# APRS-ESP32_SA8x8_Rev_C.net
KiCad netlist of a schematic drawn in EAGLE
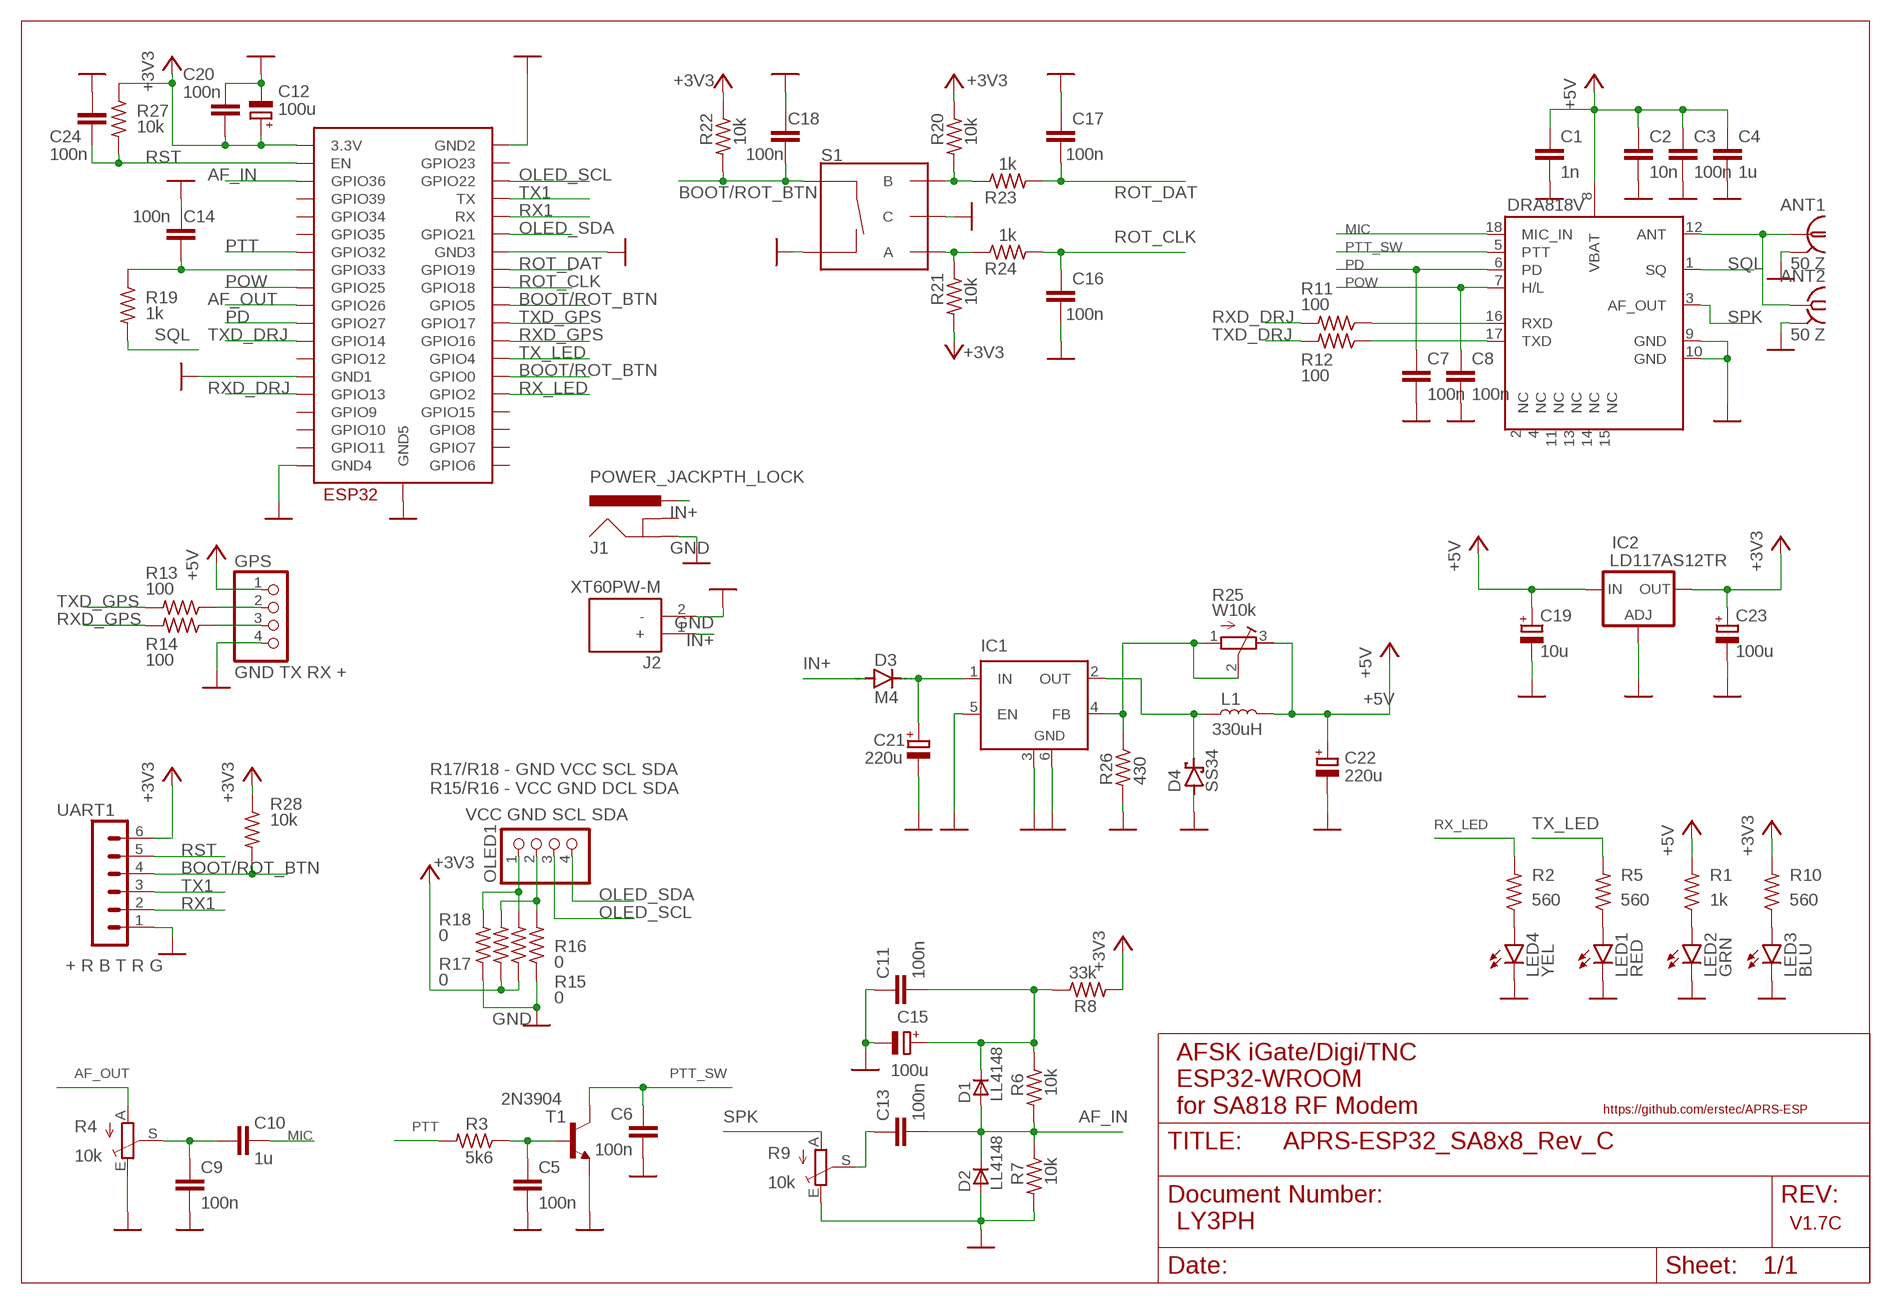
[diagram p0: schematic, sheet 1]

(export (version "E")
  (design (tool "Eeschema 10.0.6"))
  (components
    (comp (ref "ANT1")
      (value "50 Z")
      (footprint "eagle-import:LTI-SASF54GT")
      (libsource (lib "eagle-import") (part "LTI-SASF54GT"))
    )
    (comp (ref "ANT2")
      (value "50 Z")
      (footprint "eagle-import:J502-ND-142-0701-801_806")
      (fields (field (name "MF") "JOHNSON COMPONENTS") (field (name "MPN") "142-0701-801"))
      (libsource (lib "eagle-import") (part "SMA-142-0701-801/806"))
    )
    (comp (ref "C1")
      (value "1n")
      (footprint "eagle-import:C0805")
      (libsource (lib "eagle-import") (part "C-EUC0805"))
    )
    (comp (ref "C2")
      (value "10n")
      (footprint "eagle-import:C0805")
      (libsource (lib "eagle-import") (part "C-EUC0805"))
    )
    (comp (ref "C3")
      (value "100n")
      (footprint "eagle-import:C0805")
      (libsource (lib "eagle-import") (part "C-EUC0805"))
    )
    (comp (ref "C4")
      (value "1u")
      (footprint "eagle-import:C0805")
      (libsource (lib "eagle-import") (part "C-EUC0805"))
    )
    (comp (ref "C5")
      (value "100n")
      (footprint "eagle-import:C0805")
      (libsource (lib "eagle-import") (part "C-EUC0805"))
    )
    (comp (ref "C6")
      (value "100n")
      (footprint "eagle-import:C0805")
      (libsource (lib "eagle-import") (part "C-EUC0805"))
    )
    (comp (ref "C7")
      (value "100n")
      (footprint "eagle-import:C0805")
      (libsource (lib "eagle-import") (part "C-EUC0805"))
    )
    (comp (ref "C8")
      (value "100n")
      (footprint "eagle-import:C0805")
      (libsource (lib "eagle-import") (part "C-EUC0805"))
    )
    (comp (ref "C9")
      (value "100n")
      (footprint "eagle-import:C0805")
      (libsource (lib "eagle-import") (part "C-EUC0805"))
    )
    (comp (ref "C10")
      (value "1u")
      (footprint "eagle-import:C0805")
      (libsource (lib "eagle-import") (part "C-EUC0805"))
    )
    (comp (ref "C11")
      (value "100n")
      (footprint "eagle-import:C0805")
      (libsource (lib "eagle-import") (part "C-EUC0805"))
    )
    (comp (ref "C12")
      (value "100u")
      (footprint "eagle-import:SMC_D")
      (libsource (lib "eagle-import") (part "CPOL-EUSMCD"))
    )
    (comp (ref "C13")
      (value "100n")
      (footprint "eagle-import:C0805")
      (libsource (lib "eagle-import") (part "C-EUC0805"))
    )
    (comp (ref "C14")
      (value "100n")
      (footprint "eagle-import:C0805")
      (libsource (lib "eagle-import") (part "C-EUC0805"))
    )
    (comp (ref "C15")
      (value "100u")
      (footprint "eagle-import:SMC_D")
      (libsource (lib "eagle-import") (part "CPOL-EUSMCD"))
    )
    (comp (ref "C16")
      (value "100n")
      (footprint "eagle-import:C0805")
      (libsource (lib "eagle-import") (part "C-EUC0805"))
    )
    (comp (ref "C17")
      (value "100n")
      (footprint "eagle-import:C0805")
      (libsource (lib "eagle-import") (part "C-EUC0805"))
    )
    (comp (ref "C18")
      (value "100n")
      (footprint "eagle-import:C0805")
      (libsource (lib "eagle-import") (part "C-EUC0805"))
    )
    (comp (ref "C19")
      (value "10u")
      (footprint "eagle-import:PANASONIC_B")
      (libsource (lib "eagle-import") (part "CPOL-EUB"))
    )
    (comp (ref "C20")
      (value "100n")
      (footprint "eagle-import:C0805")
      (libsource (lib "eagle-import") (part "C-EUC0805"))
    )
    (comp (ref "C21")
      (value "220u")
      (footprint "eagle-import:175TMP-0808")
      (libsource (lib "eagle-import") (part "CPOL-EU175TMP-0808"))
    )
    (comp (ref "C22")
      (value "220u")
      (footprint "eagle-import:175TMP-0808")
      (libsource (lib "eagle-import") (part "CPOL-EU175TMP-0808"))
    )
    (comp (ref "C23")
      (value "100u")
      (footprint "eagle-import:PANASONIC_B")
      (libsource (lib "eagle-import") (part "CPOL-EUB"))
    )
    (comp (ref "C24")
      (value "100n")
      (footprint "eagle-import:C0805")
      (libsource (lib "eagle-import") (part "C-EUC0805"))
    )
    (comp (ref "D1")
      (value "LL4148")
      (footprint "eagle-import:SOD80_DO213AA_MINIMELF")
      (libsource (lib "eagle-import") (part "LL4148"))
    )
    (comp (ref "D2")
      (value "LL4148")
      (footprint "eagle-import:SOD80_DO213AA_MINIMELF")
      (libsource (lib "eagle-import") (part "LL4148"))
    )
    (comp (ref "D3")
      (value "M4")
      (footprint "eagle-import:SMB")
      (libsource (lib "eagle-import") (part "DIODE-SMB"))
    )
    (comp (ref "D4")
      (value "SS34")
      (footprint "eagle-import:SMB")
      (libsource (lib "eagle-import") (part "SCHOTTKY-DIODESMD"))
    )
    (comp (ref "DRA818V")
      (value "DRA818A")
      (footprint "eagle-import:DRA818A")
      (libsource (lib "eagle-import") (part "DRA818A"))
    )
    (comp (ref "GPS")
      (value "GND TX RX +")
      (footprint "eagle-import:1X04")
      (libsource (lib "eagle-import") (part "PINHD-1X4"))
    )
    (comp (ref "IC1")
      (value "LM2596S")
      (footprint "eagle-import:TO263-5")
      (libsource (lib "eagle-import") (part "LM2596S"))
    )
    (comp (ref "IC2")
      (value "LD117AS12TR")
      (footprint "eagle-import:SOT223")
      (libsource (lib "eagle-import") (part "LD117A?S12TR"))
    )
    (comp (ref "J1")
      (value "POWER_JACKPTH_LOCK")
      (footprint "eagle-import:POWER_JACK_PTH_LOCK")
      (libsource (lib "eagle-import") (part "POWER_JACKPTH_LOCK"))
    )
    (comp (ref "J2")
      (value "XT60PW-M")
      (footprint "eagle-import:AMASS_XT60PW-M")
      (fields (field (name "MF") "AMASS"))
      (libsource (lib "eagle-import") (part "XT60PW-M"))
    )
    (comp (ref "L1")
      (value "330uH")
      (footprint "eagle-import:INDUCTOR_SDR1307")
      (libsource (lib "eagle-import") (part "INDUCTOR-SDR13-27UH"))
    )
    (comp (ref "LED1")
      (value "RED")
      (footprint "eagle-import:CHIP-LED0805")
      (libsource (lib "eagle-import") (part "LEDCHIP-LED0805"))
    )
    (comp (ref "LED2")
      (value "GRN")
      (footprint "eagle-import:CHIP-LED0805")
      (libsource (lib "eagle-import") (part "LEDCHIP-LED0805"))
    )
    (comp (ref "LED3")
      (value "BLU")
      (footprint "eagle-import:CHIP-LED0805")
      (libsource (lib "eagle-import") (part "LEDCHIP-LED0805"))
    )
    (comp (ref "LED4")
      (value "YEL")
      (footprint "eagle-import:CHIP-LED0805")
      (libsource (lib "eagle-import") (part "LEDCHIP-LED0805"))
    )
    (comp (ref "OLED1")
      (value "VCC GND SCL SDA")
      (footprint "eagle-import:1X04")
      (libsource (lib "eagle-import") (part "PINHD-1X4"))
    )
    (comp (ref "R1")
      (value "1k")
      (footprint "eagle-import:R0805")
      (libsource (lib "eagle-import") (part "R-US_R0805"))
    )
    (comp (ref "R2")
      (value "560")
      (footprint "eagle-import:R0805")
      (libsource (lib "eagle-import") (part "R-US_R0805"))
    )
    (comp (ref "R3")
      (value "5k6")
      (footprint "eagle-import:R0805")
      (libsource (lib "eagle-import") (part "R-US_R0805"))
    )
    (comp (ref "R4")
      (value "10k")
      (footprint "eagle-import:CA6H")
      (libsource (lib "eagle-import") (part "TRIM_EU-CA6H"))
    )
    (comp (ref "R5")
      (value "560")
      (footprint "eagle-import:R0805")
      (libsource (lib "eagle-import") (part "R-US_R0805"))
    )
    (comp (ref "R6")
      (value "10k")
      (footprint "eagle-import:R0805")
      (libsource (lib "eagle-import") (part "R-US_R0805"))
    )
    (comp (ref "R7")
      (value "10k")
      (footprint "eagle-import:R0805")
      (libsource (lib "eagle-import") (part "R-US_R0805"))
    )
    (comp (ref "R8")
      (value "33k")
      (footprint "eagle-import:R0805")
      (libsource (lib "eagle-import") (part "R-US_R0805"))
    )
    (comp (ref "R9")
      (value "10k")
      (footprint "eagle-import:CA6H")
      (libsource (lib "eagle-import") (part "TRIM_EU-CA6H"))
    )
    (comp (ref "R10")
      (value "560")
      (footprint "eagle-import:R0805")
      (libsource (lib "eagle-import") (part "R-US_R0805"))
    )
    (comp (ref "R11")
      (value "100")
      (footprint "eagle-import:R0805")
      (libsource (lib "eagle-import") (part "R-US_R0805"))
    )
    (comp (ref "R12")
      (value "100")
      (footprint "eagle-import:R0805")
      (libsource (lib "eagle-import") (part "R-US_R0805"))
    )
    (comp (ref "R13")
      (value "100")
      (footprint "eagle-import:R0805")
      (libsource (lib "eagle-import") (part "R-US_R0805"))
    )
    (comp (ref "R14")
      (value "100")
      (footprint "eagle-import:R0805")
      (libsource (lib "eagle-import") (part "R-US_R0805"))
    )
    (comp (ref "R15")
      (value "0")
      (footprint "eagle-import:R0805")
      (libsource (lib "eagle-import") (part "R-US_R0805"))
    )
    (comp (ref "R16")
      (value "0")
      (footprint "eagle-import:R0805")
      (libsource (lib "eagle-import") (part "R-US_R0805"))
    )
    (comp (ref "R17")
      (value "0")
      (footprint "eagle-import:R0805")
      (libsource (lib "eagle-import") (part "R-US_R0805"))
    )
    (comp (ref "R18")
      (value "0")
      (footprint "eagle-import:R0805")
      (libsource (lib "eagle-import") (part "R-US_R0805"))
    )
    (comp (ref "R19")
      (value "1k")
      (footprint "eagle-import:R0805")
      (libsource (lib "eagle-import") (part "R-US_R0805"))
    )
    (comp (ref "R20")
      (value "10k")
      (footprint "eagle-import:R0805")
      (libsource (lib "eagle-import") (part "R-US_R0805"))
    )
    (comp (ref "R21")
      (value "10k")
      (footprint "eagle-import:R0805")
      (libsource (lib "eagle-import") (part "R-US_R0805"))
    )
    (comp (ref "R22")
      (value "10k")
      (footprint "eagle-import:R0805")
      (libsource (lib "eagle-import") (part "R-US_R0805"))
    )
    (comp (ref "R23")
      (value "1k")
      (footprint "eagle-import:R0805")
      (libsource (lib "eagle-import") (part "R-US_R0805"))
    )
    (comp (ref "R24")
      (value "1k")
      (footprint "eagle-import:R0805")
      (libsource (lib "eagle-import") (part "R-US_R0805"))
    )
    (comp (ref "R25")
      (value "W10k")
      (footprint "eagle-import:RTRIM64W")
      (libsource (lib "eagle-import") (part "R-TRIMM64W"))
    )
    (comp (ref "R26")
      (value "430")
      (footprint "eagle-import:R0805")
      (libsource (lib "eagle-import") (part "R-US_R0805"))
    )
    (comp (ref "R27")
      (value "10k")
      (footprint "eagle-import:R0805")
      (libsource (lib "eagle-import") (part "R-US_R0805"))
    )
    (comp (ref "R28")
      (value "10k")
      (footprint "eagle-import:R0805")
      (libsource (lib "eagle-import") (part "R-US_R0805"))
    )
    (comp (ref "S1")
      (value "ENCODER-SWITCH")
      (footprint "eagle-import:ROTARY_ENC_PLAIN")
      (libsource (lib "eagle-import") (part "ENCODER-SWITCH"))
    )
    (comp (ref "T1")
      (value "2N3904")
      (footprint "eagle-import:SOT23-BEC")
      (libsource (lib "eagle-import") (part "-NPN-SOT23-BECMMBT3904LT1"))
    )
    (comp (ref "U$2")
      (value "ESP32-WROOM")
      (footprint "eagle-import:ESP32-WROOM")
      (libsource (lib "eagle-import") (part "ESP32-WROOM"))
    )
    (comp (ref "UART1")
      (value "+ R B T R G")
      (footprint "eagle-import:MA06-1")
      (libsource (lib "eagle-import") (part "MA06-1"))
    )
  )
  (nets
    (net (code "1") (name "+3V3") (class "Default")
      (node (ref "C12") (pin "+") (pinfunction "+_+") (pintype "passive"))
      (node (ref "C20") (pin "2") (pinfunction "2_2") (pintype "passive"))
      (node (ref "C23") (pin "+") (pinfunction "+_+") (pintype "passive"))
      (node (ref "IC2") (pin "4") (pinfunction "OUT_4") (pintype "passive"))
      (node (ref "R10") (pin "2") (pinfunction "2_2") (pintype "passive"))
      (node (ref "R15") (pin "1") (pinfunction "1_1") (pintype "passive"))
      (node (ref "R17") (pin "1") (pinfunction "1_1") (pintype "passive"))
      (node (ref "R20") (pin "1") (pinfunction "1_1") (pintype "passive"))
      (node (ref "R21") (pin "2") (pinfunction "2_2") (pintype "passive"))
      (node (ref "R22") (pin "1") (pinfunction "1_1") (pintype "passive"))
      (node (ref "R27") (pin "1") (pinfunction "1_1") (pintype "passive"))
      (node (ref "R28") (pin "1") (pinfunction "1_1") (pintype "passive"))
      (node (ref "R8") (pin "2") (pinfunction "2_2") (pintype "passive"))
      (node (ref "U$2") (pin "3V3") (pinfunction "3.3V_3V3") (pintype "bidirectional"))
      (node (ref "UART1") (pin "6") (pinfunction "6_6") (pintype "passive"))
    )
    (net (code "2") (name "+5V") (class "Default")
      (node (ref "C1") (pin "1") (pinfunction "1_1") (pintype "passive"))
      (node (ref "C19") (pin "+") (pinfunction "+_+") (pintype "passive"))
      (node (ref "C2") (pin "1") (pinfunction "1_1") (pintype "passive"))
      (node (ref "C22") (pin "+") (pinfunction "+_+") (pintype "passive"))
      (node (ref "C3") (pin "1") (pinfunction "1_1") (pintype "passive"))
      (node (ref "C4") (pin "1") (pinfunction "1_1") (pintype "passive"))
      (node (ref "DRA818V") (pin "8") (pinfunction "VBAT_8") (pintype "bidirectional"))
      (node (ref "GPS") (pin "1") (pinfunction "1_1") (pintype "passive"))
      (node (ref "IC2") (pin "3") (pinfunction "IN_3") (pintype "input"))
      (node (ref "L1") (pin "P$2") (pinfunction "2_P$2") (pintype "passive"))
      (node (ref "R1") (pin "2") (pinfunction "2_2") (pintype "passive"))
      (node (ref "R25") (pin "3") (pinfunction "E_3") (pintype "passive"))
    )
    (net (code "3") (name "/AF_IN") (class "Default")
      (node (ref "C13") (pin "2") (pinfunction "2_2") (pintype "passive"))
      (node (ref "D1") (pin "A") (pinfunction "A_A") (pintype "passive"))
      (node (ref "D2") (pin "C") (pinfunction "C_C") (pintype "passive"))
      (node (ref "R6") (pin "2") (pinfunction "2_2") (pintype "passive"))
      (node (ref "R7") (pin "1") (pinfunction "1_1") (pintype "passive"))
      (node (ref "U$2") (pin "SENSOR_VP") (pinfunction "GPIO36_SENSOR_VP") (pintype "bidirectional"))
    )
    (net (code "4") (name "/AF_OUT") (class "Default")
      (node (ref "R4") (pin "A") (pinfunction "A_A") (pintype "passive"))
      (node (ref "U$2") (pin "IO26") (pinfunction "GPIO26_IO26") (pintype "bidirectional"))
    )
    (net (code "5") (name "/BOOT{slash}ROT_BTN") (class "Default")
      (node (ref "C18") (pin "2") (pinfunction "2_2") (pintype "passive"))
      (node (ref "R22") (pin "2") (pinfunction "2_2") (pintype "passive"))
      (node (ref "R28") (pin "2") (pinfunction "2_2") (pintype "passive"))
      (node (ref "S1") (pin "SW+") (pinfunction "SW+_SW+") (pintype "bidirectional"))
      (node (ref "U$2") (pin "IO0") (pinfunction "GPIO0_IO0") (pintype "bidirectional"))
      (node (ref "U$2") (pin "IO5") (pinfunction "GPIO5_IO5") (pintype "bidirectional"))
      (node (ref "UART1") (pin "4") (pinfunction "4_4") (pintype "passive"))
    )
    (net (code "6") (name "/IN+") (class "Default")
      (node (ref "D3") (pin "A") (pinfunction "A_A") (pintype "passive"))
      (node (ref "J1") (pin "PWR") (pinfunction "PWR_PWR") (pintype "bidirectional"))
      (node (ref "J2") (pin "1") (pinfunction "+_1") (pintype "passive"))
    )
    (net (code "7") (name "/MIC") (class "Default")
      (node (ref "C10") (pin "2") (pinfunction "2_2") (pintype "passive"))
      (node (ref "DRA818V") (pin "18") (pinfunction "MIC_IN_18") (pintype "bidirectional"))
    )
    (net (code "8") (name "/OLED_SCL") (class "Default")
      (node (ref "OLED1") (pin "3") (pinfunction "3_3") (pintype "passive"))
      (node (ref "U$2") (pin "IO22") (pinfunction "GPIO22_IO22") (pintype "bidirectional"))
    )
    (net (code "9") (name "/OLED_SDA") (class "Default")
      (node (ref "OLED1") (pin "4") (pinfunction "4_4") (pintype "passive"))
      (node (ref "U$2") (pin "IO21") (pinfunction "GPIO21_IO21") (pintype "bidirectional"))
    )
    (net (code "10") (name "/PD") (class "Default")
      (node (ref "C7") (pin "1") (pinfunction "1_1") (pintype "passive"))
      (node (ref "DRA818V") (pin "6") (pinfunction "PD_6") (pintype "bidirectional"))
      (node (ref "U$2") (pin "IO27") (pinfunction "GPIO27_IO27") (pintype "bidirectional"))
    )
    (net (code "11") (name "/POW") (class "Default")
      (node (ref "C8") (pin "1") (pinfunction "1_1") (pintype "passive"))
      (node (ref "DRA818V") (pin "7") (pinfunction "H/L_7") (pintype "bidirectional"))
      (node (ref "U$2") (pin "IO25") (pinfunction "GPIO25_IO25") (pintype "bidirectional"))
    )
    (net (code "12") (name "/PTT") (class "Default")
      (node (ref "R3") (pin "2") (pinfunction "2_2") (pintype "passive"))
      (node (ref "U$2") (pin "IO32") (pinfunction "GPIO32_IO32") (pintype "bidirectional"))
    )
    (net (code "13") (name "/PTT_SW") (class "Default")
      (node (ref "C6") (pin "1") (pinfunction "1_1") (pintype "passive"))
      (node (ref "DRA818V") (pin "5") (pinfunction "PTT_5") (pintype "bidirectional"))
      (node (ref "T1") (pin "C") (pinfunction "C_C") (pintype "passive"))
    )
    (net (code "14") (name "/ROT_CLK") (class "Default")
      (node (ref "C16") (pin "1") (pinfunction "1_1") (pintype "passive"))
      (node (ref "R24") (pin "2") (pinfunction "2_2") (pintype "passive"))
      (node (ref "U$2") (pin "IO18") (pinfunction "GPIO18_IO18") (pintype "bidirectional"))
    )
    (net (code "15") (name "/ROT_DAT") (class "Default")
      (node (ref "C17") (pin "2") (pinfunction "2_2") (pintype "passive"))
      (node (ref "R23") (pin "2") (pinfunction "2_2") (pintype "passive"))
      (node (ref "U$2") (pin "IO19") (pinfunction "GPIO19_IO19") (pintype "bidirectional"))
    )
    (net (code "16") (name "/RST") (class "Default")
      (node (ref "C24") (pin "2") (pinfunction "2_2") (pintype "passive"))
      (node (ref "R27") (pin "2") (pinfunction "2_2") (pintype "passive"))
      (node (ref "U$2") (pin "EN") (pinfunction "EN_EN") (pintype "bidirectional"))
      (node (ref "UART1") (pin "5") (pinfunction "5_5") (pintype "passive"))
    )
    (net (code "17") (name "/RX1") (class "Default")
      (node (ref "U$2") (pin "RX") (pinfunction "RX_RX") (pintype "bidirectional"))
      (node (ref "UART1") (pin "2") (pinfunction "2_2") (pintype "passive"))
    )
    (net (code "18") (name "/RXD_DRJ") (class "Default")
      (node (ref "R11") (pin "2") (pinfunction "2_2") (pintype "passive"))
      (node (ref "U$2") (pin "IO13") (pinfunction "GPIO13_IO13") (pintype "bidirectional"))
    )
    (net (code "19") (name "/RXD_GPS") (class "Default")
      (node (ref "R14") (pin "2") (pinfunction "2_2") (pintype "passive"))
      (node (ref "U$2") (pin "IO16") (pinfunction "GPIO16_IO16") (pintype "bidirectional"))
    )
    (net (code "20") (name "/RX_LED") (class "Default")
      (node (ref "R2") (pin "2") (pinfunction "2_2") (pintype "passive"))
      (node (ref "U$2") (pin "IO2") (pinfunction "GPIO2_IO2") (pintype "bidirectional"))
    )
    (net (code "21") (name "/SPK") (class "Default")
      (node (ref "DRA818V") (pin "3") (pinfunction "AF_OUT_3") (pintype "bidirectional"))
      (node (ref "R9") (pin "A") (pinfunction "A_A") (pintype "passive"))
    )
    (net (code "22") (name "/SQL") (class "Default")
      (node (ref "DRA818V") (pin "1") (pinfunction "SQ_1") (pintype "bidirectional"))
      (node (ref "R19") (pin "2") (pinfunction "2_2") (pintype "passive"))
    )
    (net (code "23") (name "/TX1") (class "Default")
      (node (ref "U$2") (pin "TX") (pinfunction "TX_TX") (pintype "bidirectional"))
      (node (ref "UART1") (pin "3") (pinfunction "3_3") (pintype "passive"))
    )
    (net (code "24") (name "/TXD_DRJ") (class "Default")
      (node (ref "R12") (pin "2") (pinfunction "2_2") (pintype "passive"))
      (node (ref "U$2") (pin "IO14") (pinfunction "GPIO14_IO14") (pintype "bidirectional"))
    )
    (net (code "25") (name "/TXD_GPS") (class "Default")
      (node (ref "R13") (pin "2") (pinfunction "2_2") (pintype "passive"))
      (node (ref "U$2") (pin "IO17") (pinfunction "GPIO17_IO17") (pintype "bidirectional"))
    )
    (net (code "26") (name "/TX_LED") (class "Default")
      (node (ref "R5") (pin "2") (pinfunction "2_2") (pintype "passive"))
      (node (ref "U$2") (pin "IO4") (pinfunction "GPIO4_IO4") (pintype "bidirectional"))
    )
    (net (code "27") (name "GND") (class "Default")
      (node (ref "ANT1") (pin "2") (pinfunction "2_2") (pintype "passive"))
      (node (ref "ANT1") (pin "3") (pinfunction "2_3") (pintype "passive"))
      (node (ref "ANT1") (pin "4") (pinfunction "2_4") (pintype "passive"))
      (node (ref "ANT1") (pin "5") (pinfunction "2_5") (pintype "passive"))
      (node (ref "ANT2") (pin "G@1") (pinfunction "2_G@1") (pintype "passive"))
      (node (ref "ANT2") (pin "G@2") (pinfunction "2_G@2") (pintype "passive"))
      (node (ref "ANT2") (pin "G@3") (pinfunction "2_G@3") (pintype "passive"))
      (node (ref "ANT2") (pin "G@4") (pinfunction "2_G@4") (pintype "passive"))
      (node (ref "C1") (pin "2") (pinfunction "2_2") (pintype "passive"))
      (node (ref "C11") (pin "1") (pinfunction "1_1") (pintype "passive"))
      (node (ref "C12") (pin "-") (pinfunction "-_-") (pintype "passive"))
      (node (ref "C14") (pin "2") (pinfunction "2_2") (pintype "passive"))
      (node (ref "C15") (pin "-") (pinfunction "-_-") (pintype "passive"))
      (node (ref "C16") (pin "2") (pinfunction "2_2") (pintype "passive"))
      (node (ref "C17") (pin "1") (pinfunction "1_1") (pintype "passive"))
      (node (ref "C18") (pin "1") (pinfunction "1_1") (pintype "passive"))
      (node (ref "C19") (pin "-") (pinfunction "-_-") (pintype "passive"))
      (node (ref "C2") (pin "2") (pinfunction "2_2") (pintype "passive"))
      (node (ref "C20") (pin "1") (pinfunction "1_1") (pintype "passive"))
      (node (ref "C21") (pin "-") (pinfunction "-_-") (pintype "passive"))
      (node (ref "C22") (pin "-") (pinfunction "-_-") (pintype "passive"))
      (node (ref "C23") (pin "-") (pinfunction "-_-") (pintype "passive"))
      (node (ref "C24") (pin "1") (pinfunction "1_1") (pintype "passive"))
      (node (ref "C3") (pin "2") (pinfunction "2_2") (pintype "passive"))
      (node (ref "C4") (pin "2") (pinfunction "2_2") (pintype "passive"))
      (node (ref "C5") (pin "2") (pinfunction "2_2") (pintype "passive"))
      (node (ref "C6") (pin "2") (pinfunction "2_2") (pintype "passive"))
      (node (ref "C7") (pin "2") (pinfunction "2_2") (pintype "passive"))
      (node (ref "C8") (pin "2") (pinfunction "2_2") (pintype "passive"))
      (node (ref "C9") (pin "2") (pinfunction "2_2") (pintype "passive"))
      (node (ref "D2") (pin "A") (pinfunction "A_A") (pintype "passive"))
      (node (ref "D4") (pin "A") (pinfunction "A_A") (pintype "passive"))
      (node (ref "DRA818V") (pin "10") (pinfunction "GND_10") (pintype "bidirectional"))
      (node (ref "DRA818V") (pin "9") (pinfunction "GND_9") (pintype "bidirectional"))
      (node (ref "GPS") (pin "4") (pinfunction "4_4") (pintype "passive"))
      (node (ref "IC1") (pin "3") (pinfunction "GND_3") (pintype "power_in"))
      (node (ref "IC1") (pin "5") (pinfunction "EN_5") (pintype "input"))
      (node (ref "IC1") (pin "6") (pinfunction "GND_6") (pintype "power_in"))
      (node (ref "IC2") (pin "1") (pinfunction "ADJ_1") (pintype "input"))
      (node (ref "J1") (pin "GND") (pinfunction "GND_GND") (pintype "bidirectional"))
      (node (ref "J2") (pin "2") (pinfunction "-_2") (pintype "passive"))
      (node (ref "LED1") (pin "C") (pinfunction "C_C") (pintype "passive"))
      (node (ref "LED2") (pin "C") (pinfunction "C_C") (pintype "passive"))
      (node (ref "LED3") (pin "C") (pinfunction "C_C") (pintype "passive"))
      (node (ref "LED4") (pin "C") (pinfunction "C_C") (pintype "passive"))
      (node (ref "R16") (pin "1") (pinfunction "1_1") (pintype "passive"))
      (node (ref "R18") (pin "1") (pinfunction "1_1") (pintype "passive"))
      (node (ref "R26") (pin "2") (pinfunction "2_2") (pintype "passive"))
      (node (ref "R4") (pin "E") (pinfunction "E_E") (pintype "passive"))
      (node (ref "R7") (pin "2") (pinfunction "2_2") (pintype "passive"))
      (node (ref "R9") (pin "E") (pinfunction "E_E") (pintype "passive"))
      (node (ref "S1") (pin "C") (pinfunction "C_C") (pintype "bidirectional"))
      (node (ref "S1") (pin "SW-") (pinfunction "SW-_SW-") (pintype "bidirectional"))
      (node (ref "T1") (pin "E") (pinfunction "E_E") (pintype "passive"))
      (node (ref "U$2") (pin "GND1") (pinfunction "GND1_GND1") (pintype "bidirectional"))
      (node (ref "U$2") (pin "GND2") (pinfunction "GND2_GND2") (pintype "bidirectional"))
      (node (ref "U$2") (pin "GND3") (pinfunction "GND3_GND3") (pintype "bidirectional"))
      (node (ref "U$2") (pin "GND4") (pinfunction "GND4_GND4") (pintype "bidirectional"))
      (node (ref "U$2") (pin "GND5") (pinfunction "GND5_GND5") (pintype "bidirectional"))
      (node (ref "UART1") (pin "1") (pinfunction "1_1") (pintype "passive"))
    )
    (net (code "28") (name "Net-(C5-Pad1)") (class "Default")
      (node (ref "C5") (pin "1") (pinfunction "1_1") (pintype "passive"))
      (node (ref "R3") (pin "1") (pinfunction "1_1") (pintype "passive"))
      (node (ref "T1") (pin "B") (pinfunction "B_B") (pintype "passive"))
    )
    (net (code "29") (name "Net-(C10-Pad1)") (class "Default")
      (node (ref "C10") (pin "1") (pinfunction "1_1") (pintype "passive"))
      (node (ref "C9") (pin "1") (pinfunction "1_1") (pintype "passive"))
      (node (ref "R4") (pin "S") (pinfunction "S_S") (pintype "passive"))
    )
    (net (code "30") (name "Net-(C11-Pad2)") (class "Default")
      (node (ref "C11") (pin "2") (pinfunction "2_2") (pintype "passive"))
      (node (ref "C15") (pin "+") (pinfunction "+_+") (pintype "passive"))
      (node (ref "D1") (pin "C") (pinfunction "C_C") (pintype "passive"))
      (node (ref "R6") (pin "1") (pinfunction "1_1") (pintype "passive"))
      (node (ref "R8") (pin "1") (pinfunction "1_1") (pintype "passive"))
    )
    (net (code "31") (name "Net-(C13-Pad1)") (class "Default")
      (node (ref "C13") (pin "1") (pinfunction "1_1") (pintype "passive"))
      (node (ref "R9") (pin "S") (pinfunction "S_S") (pintype "passive"))
    )
    (net (code "32") (name "Net-(DRA818V-ANT)") (class "Default")
      (node (ref "ANT1") (pin "1") (pinfunction "1_1") (pintype "passive"))
      (node (ref "ANT2") (pin "1") (pinfunction "1_1") (pintype "passive"))
      (node (ref "DRA818V") (pin "12") (pinfunction "ANT_12") (pintype "bidirectional"))
    )
    (net (code "33") (name "Net-(DRA818V-RXD)") (class "Default")
      (node (ref "DRA818V") (pin "16") (pinfunction "RXD_16") (pintype "bidirectional"))
      (node (ref "R11") (pin "1") (pinfunction "1_1") (pintype "passive"))
    )
    (net (code "34") (name "Net-(DRA818V-TXD)") (class "Default")
      (node (ref "DRA818V") (pin "17") (pinfunction "TXD_17") (pintype "bidirectional"))
      (node (ref "R12") (pin "1") (pinfunction "1_1") (pintype "passive"))
    )
    (net (code "35") (name "Net-(GPS-Pad2)") (class "Default")
      (node (ref "GPS") (pin "2") (pinfunction "2_2") (pintype "passive"))
      (node (ref "R13") (pin "1") (pinfunction "1_1") (pintype "passive"))
    )
    (net (code "36") (name "Net-(GPS-Pad3)") (class "Default")
      (node (ref "GPS") (pin "3") (pinfunction "3_3") (pintype "passive"))
      (node (ref "R14") (pin "1") (pinfunction "1_1") (pintype "passive"))
    )
    (net (code "37") (name "Net-(IC1-FB)") (class "Default")
      (node (ref "IC1") (pin "4") (pinfunction "FB_4") (pintype "input"))
      (node (ref "R25") (pin "1") (pinfunction "A_1") (pintype "passive"))
      (node (ref "R25") (pin "2") (pinfunction "S_2") (pintype "passive"))
      (node (ref "R26") (pin "1") (pinfunction "1_1") (pintype "passive"))
    )
    (net (code "38") (name "Net-(IC1-IN)") (class "Default")
      (node (ref "C21") (pin "+") (pinfunction "+_+") (pintype "passive"))
      (node (ref "D3") (pin "C") (pinfunction "C_C") (pintype "passive"))
      (node (ref "IC1") (pin "1") (pinfunction "IN_1") (pintype "input"))
    )
    (net (code "39") (name "Net-(IC1-OUT)") (class "Default")
      (node (ref "D4") (pin "C") (pinfunction "C_C") (pintype "passive"))
      (node (ref "IC1") (pin "2") (pinfunction "OUT_2") (pintype "output"))
      (node (ref "L1") (pin "P$1") (pinfunction "1_P$1") (pintype "passive"))
    )
    (net (code "40") (name "Net-(LED1-PadA)") (class "Default")
      (node (ref "LED1") (pin "A") (pinfunction "A_A") (pintype "passive"))
      (node (ref "R5") (pin "1") (pinfunction "1_1") (pintype "passive"))
    )
    (net (code "41") (name "Net-(LED2-PadA)") (class "Default")
      (node (ref "LED2") (pin "A") (pinfunction "A_A") (pintype "passive"))
      (node (ref "R1") (pin "1") (pinfunction "1_1") (pintype "passive"))
    )
    (net (code "42") (name "Net-(LED3-PadA)") (class "Default")
      (node (ref "LED3") (pin "A") (pinfunction "A_A") (pintype "passive"))
      (node (ref "R10") (pin "1") (pinfunction "1_1") (pintype "passive"))
    )
    (net (code "43") (name "Net-(LED4-PadA)") (class "Default")
      (node (ref "LED4") (pin "A") (pinfunction "A_A") (pintype "passive"))
      (node (ref "R2") (pin "1") (pinfunction "1_1") (pintype "passive"))
    )
    (net (code "44") (name "Net-(OLED1-Pad1)") (class "Default")
      (node (ref "OLED1") (pin "1") (pinfunction "1_1") (pintype "passive"))
      (node (ref "R15") (pin "2") (pinfunction "2_2") (pintype "passive"))
      (node (ref "R18") (pin "2") (pinfunction "2_2") (pintype "passive"))
    )
    (net (code "45") (name "Net-(OLED1-Pad2)") (class "Default")
      (node (ref "OLED1") (pin "2") (pinfunction "2_2") (pintype "passive"))
      (node (ref "R16") (pin "2") (pinfunction "2_2") (pintype "passive"))
      (node (ref "R17") (pin "2") (pinfunction "2_2") (pintype "passive"))
    )
    (net (code "46") (name "Net-(R20-Pad2)") (class "Default")
      (node (ref "R20") (pin "2") (pinfunction "2_2") (pintype "passive"))
      (node (ref "R23") (pin "1") (pinfunction "1_1") (pintype "passive"))
      (node (ref "S1") (pin "B") (pinfunction "B_B") (pintype "bidirectional"))
    )
    (net (code "47") (name "Net-(R21-Pad1)") (class "Default")
      (node (ref "R21") (pin "1") (pinfunction "1_1") (pintype "passive"))
      (node (ref "R24") (pin "1") (pinfunction "1_1") (pintype "passive"))
      (node (ref "S1") (pin "A") (pinfunction "A_A") (pintype "bidirectional"))
    )
    (net (code "48") (name "Net-(U$2-GPIO33)") (class "Default")
      (node (ref "C14") (pin "1") (pinfunction "1_1") (pintype "passive"))
      (node (ref "R19") (pin "1") (pinfunction "1_1") (pintype "passive"))
      (node (ref "U$2") (pin "IO33") (pinfunction "GPIO33_IO33") (pintype "bidirectional"))
    )
    (net (code "49") (name "unconnected-(DRA818V-NC-Pad2)") (class "Default")
      (node (ref "DRA818V") (pin "2") (pinfunction "NC_2") (pintype "bidirectional"))
    )
    (net (code "50") (name "unconnected-(DRA818V-NC-Pad4)") (class "Default")
      (node (ref "DRA818V") (pin "4") (pinfunction "NC_4") (pintype "bidirectional"))
    )
    (net (code "51") (name "unconnected-(DRA818V-NC-Pad11)") (class "Default")
      (node (ref "DRA818V") (pin "11") (pinfunction "NC_11") (pintype "bidirectional"))
    )
    (net (code "52") (name "unconnected-(DRA818V-NC-Pad13)") (class "Default")
      (node (ref "DRA818V") (pin "13") (pinfunction "NC_13") (pintype "bidirectional"))
    )
    (net (code "53") (name "unconnected-(DRA818V-NC-Pad14)") (class "Default")
      (node (ref "DRA818V") (pin "14") (pinfunction "NC_14") (pintype "bidirectional"))
    )
    (net (code "54") (name "unconnected-(DRA818V-NC-Pad15)") (class "Default")
      (node (ref "DRA818V") (pin "15") (pinfunction "NC_15") (pintype "bidirectional"))
    )
    (net (code "55") (name "unconnected-(J1-PadGNDBREAK)") (class "Default")
      (node (ref "J1") (pin "GNDBREAK") (pinfunction "GNDBREAK_GNDBREAK") (pintype "bidirectional"))
    )
    (net (code "56") (name "unconnected-(U$2-GPIO6-PadCLK)") (class "Default")
      (node (ref "U$2") (pin "CLK") (pinfunction "GPIO6_CLK") (pintype "bidirectional"))
    )
    (net (code "57") (name "unconnected-(U$2-GPIO7-PadSD0)") (class "Default")
      (node (ref "U$2") (pin "SD0") (pinfunction "GPIO7_SD0") (pintype "bidirectional"))
    )
    (net (code "58") (name "unconnected-(U$2-GPIO8-PadSD1)") (class "Default")
      (node (ref "U$2") (pin "SD1") (pinfunction "GPIO8_SD1") (pintype "bidirectional"))
    )
    (net (code "59") (name "unconnected-(U$2-GPIO9-PadSD2)") (class "Default")
      (node (ref "U$2") (pin "SD2") (pinfunction "GPIO9_SD2") (pintype "bidirectional"))
    )
    (net (code "60") (name "unconnected-(U$2-GPIO10-PadSD3)") (class "Default")
      (node (ref "U$2") (pin "SD3") (pinfunction "GPIO10_SD3") (pintype "bidirectional"))
    )
    (net (code "61") (name "unconnected-(U$2-GPIO11-PadCMD)") (class "Default")
      (node (ref "U$2") (pin "CMD") (pinfunction "GPIO11_CMD") (pintype "bidirectional"))
    )
    (net (code "62") (name "unconnected-(U$2-GPIO12-PadIO12)") (class "Default")
      (node (ref "U$2") (pin "IO12") (pinfunction "GPIO12_IO12") (pintype "bidirectional"))
    )
    (net (code "63") (name "unconnected-(U$2-GPIO15-PadIO15)") (class "Default")
      (node (ref "U$2") (pin "IO15") (pinfunction "GPIO15_IO15") (pintype "bidirectional"))
    )
    (net (code "64") (name "unconnected-(U$2-GPIO23-PadIO23)") (class "Default")
      (node (ref "U$2") (pin "IO23") (pinfunction "GPIO23_IO23") (pintype "bidirectional"))
    )
    (net (code "65") (name "unconnected-(U$2-GPIO34-PadIO34)") (class "Default")
      (node (ref "U$2") (pin "IO34") (pinfunction "GPIO34_IO34") (pintype "bidirectional"))
    )
    (net (code "66") (name "unconnected-(U$2-GPIO35-PadIO35)") (class "Default")
      (node (ref "U$2") (pin "IO35") (pinfunction "GPIO35_IO35") (pintype "bidirectional"))
    )
    (net (code "67") (name "unconnected-(U$2-GPIO39-PadSENSOR_VN)") (class "Default")
      (node (ref "U$2") (pin "SENSOR_VN") (pinfunction "GPIO39_SENSOR_VN") (pintype "bidirectional"))
    )
  )
)
